# div_mod.net
KiCad netlist of a schematic drawn in EAGLE
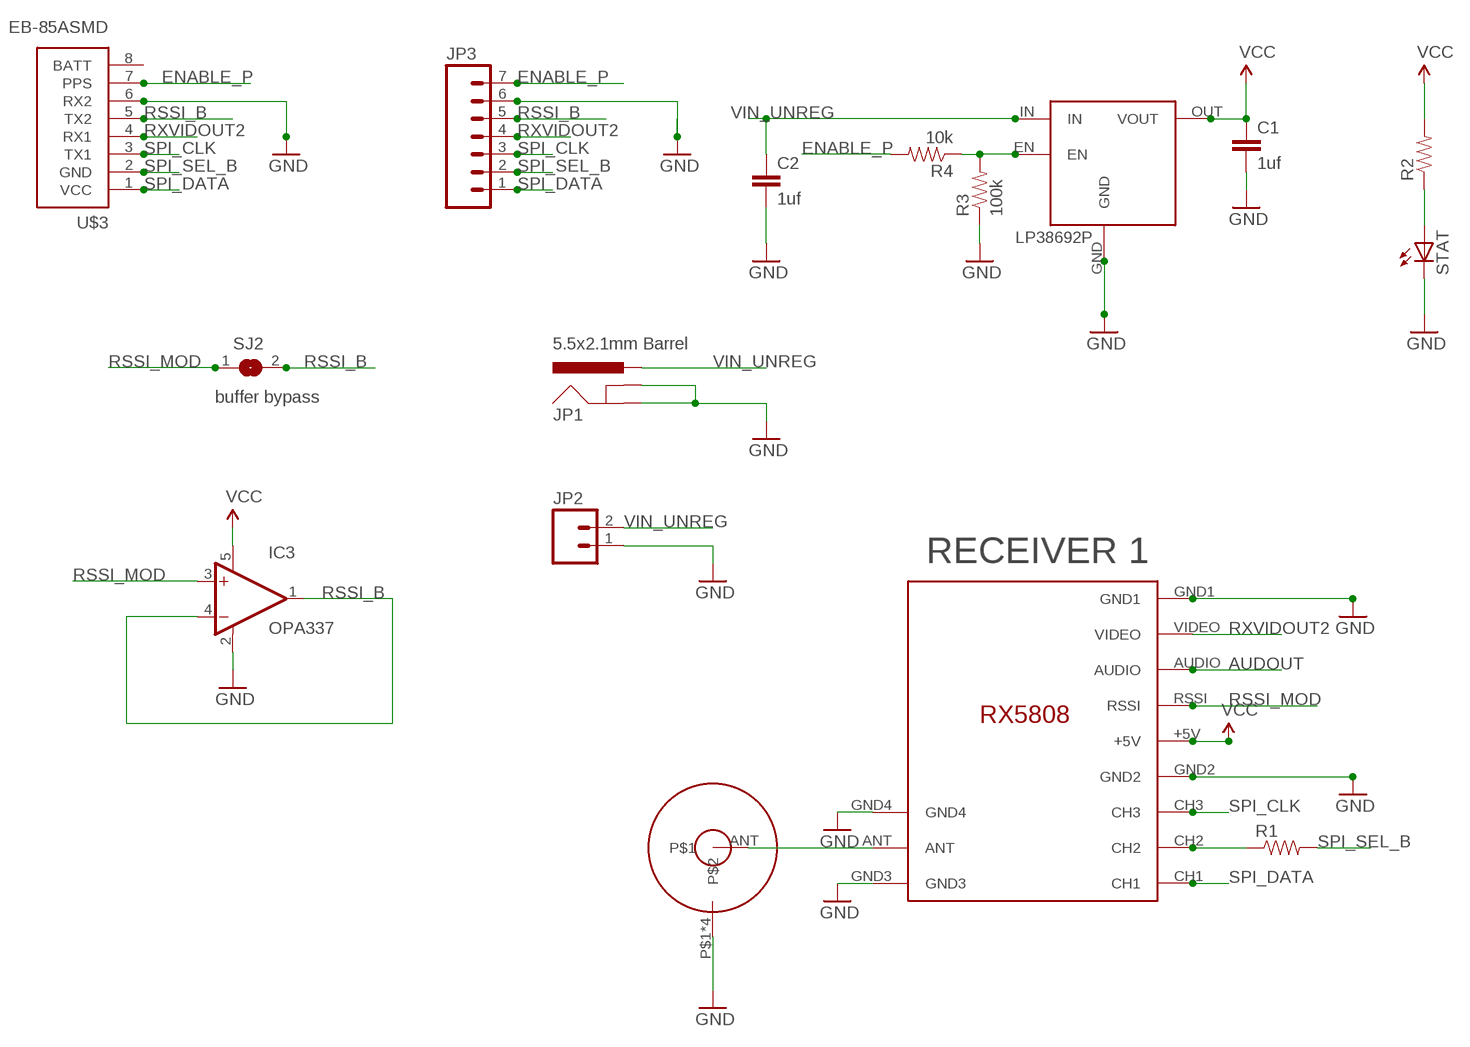
[diagram p0: schematic, sheet 1]

(export (version "E")
  (design (tool "Eeschema 10.0.6"))
  (components
    (comp (ref "C1")
      (value "1uf")
      (footprint "eagle-import:0805")
      (libsource (lib "eagle-import") (part "CAP0805"))
    )
    (comp (ref "C2")
      (value "1uf")
      (footprint "eagle-import:0805")
      (libsource (lib "eagle-import") (part "CAP0805"))
    )
    (comp (ref "IC3")
      (value "OPA336N")
      (footprint "eagle-import:SOT23-5")
      (fields (field (name "MPN") "OPA336NA"))
      (libsource (lib "eagle-import") (part "OPA336N"))
    )
    (comp (ref "JP1")
      (value "5.5x2.1mm Barrel")
      (footprint "eagle-import:POWER_JACK_SMD")
      (libsource (lib "eagle-import") (part "POWER_JACKSMD"))
    )
    (comp (ref "JP2")
      (value "M02PTH")
      (footprint "eagle-import:1X02")
      (libsource (lib "eagle-import") (part "M02PTH"))
    )
    (comp (ref "JP3")
      (value "M07")
      (footprint "eagle-import:1X07")
      (libsource (lib "eagle-import") (part "M07"))
    )
    (comp (ref "R1")
      (value "RESISTOR0805-RES")
      (footprint "eagle-import:0805")
      (libsource (lib "eagle-import") (part "RESISTOR0805-RES"))
    )
    (comp (ref "R2")
      (value "RESISTOR0805-RES")
      (footprint "eagle-import:0805")
      (libsource (lib "eagle-import") (part "RESISTOR0805-RES"))
    )
    (comp (ref "R3")
      (value "100k")
      (footprint "eagle-import:0805")
      (libsource (lib "eagle-import") (part "RESISTOR0805-RES"))
    )
    (comp (ref "R4")
      (value "10k")
      (footprint "eagle-import:0805")
      (libsource (lib "eagle-import") (part "RESISTOR0805-RES"))
    )
    (comp (ref "RECEIVER_A")
      (value "RX5808_A")
      (footprint "eagle-import:RX5808")
      (libsource (lib "eagle-import") (part "RX5808"))
    )
    (comp (ref "SJ2") (value "SJ") (footprint "eagle-import:SJ") (libsource (lib "eagle-import") (part "SJ")))
    (comp (ref "STAT")
      (value "LEDCHIP-LED0805")
      (footprint "eagle-import:CHIP-LED0805")
      (libsource (lib "eagle-import") (part "LEDCHIP-LED0805"))
    )
    (comp (ref "U$1")
      (value "SMA_ANTENNA")
      (footprint "eagle-import:SMA_CONNECTOR")
      (libsource (lib "eagle-import") (part "SMA_ANTENNA"))
    )
    (comp (ref "U$3")
      (value "EB-85ASMD")
      (footprint "eagle-import:EB-85A")
      (libsource (lib "eagle-import") (part "EB-85ASMD"))
    )
    (comp (ref "V1")
      (value "LP38692P")
      (footprint "eagle-import:TO252-51")
      (libsource (lib "eagle-import") (part "LP38692P"))
    )
  )
  (nets
    (net (code "1") (name "/AUDOUT") (class "Default")
      (node (ref "RECEIVER_A") (pin "AUDIO") (pinfunction "AUDIO_AUDIO") (pintype "bidirectional"))
    )
    (net (code "2") (name "/BATT") (class "Default")
      (node (ref "U$3") (pin "8") (pinfunction "BATT_8") (pintype "power_in"))
    )
    (net (code "3") (name "/ENABLE_P") (class "Default")
      (node (ref "JP3") (pin "7") (pinfunction "7_7") (pintype "passive"))
      (node (ref "R4") (pin "2") (pinfunction "2_2") (pintype "passive"))
      (node (ref "U$3") (pin "7") (pinfunction "PPS_7") (pintype "output"))
    )
    (net (code "4") (name "/RSSI_B") (class "Default")
      (node (ref "IC3") (pin "1") (pinfunction "OUT_1") (pintype "output"))
      (node (ref "IC3") (pin "4") (pinfunction "-IN_4") (pintype "input"))
      (node (ref "JP3") (pin "5") (pinfunction "5_5") (pintype "passive"))
      (node (ref "SJ2") (pin "2") (pinfunction "2_2") (pintype "passive"))
      (node (ref "U$3") (pin "5") (pinfunction "TX2_5") (pintype "output"))
    )
    (net (code "5") (name "/RSSI_MOD") (class "Default")
      (node (ref "IC3") (pin "3") (pinfunction "+IN_3") (pintype "input"))
      (node (ref "RECEIVER_A") (pin "RSSI") (pinfunction "RSSI_RSSI") (pintype "bidirectional"))
      (node (ref "SJ2") (pin "1") (pinfunction "1_1") (pintype "passive"))
    )
    (net (code "6") (name "/RXVIDOUT2") (class "Default")
      (node (ref "JP3") (pin "4") (pinfunction "4_4") (pintype "passive"))
      (node (ref "RECEIVER_A") (pin "VIDEO") (pinfunction "VIDEO_VIDEO") (pintype "bidirectional"))
      (node (ref "U$3") (pin "4") (pinfunction "RX1_4") (pintype "input"))
    )
    (net (code "7") (name "/SPI_CLK") (class "Default")
      (node (ref "JP3") (pin "3") (pinfunction "3_3") (pintype "passive"))
      (node (ref "RECEIVER_A") (pin "CH3") (pinfunction "CH3_CH3") (pintype "bidirectional"))
      (node (ref "U$3") (pin "3") (pinfunction "TX1_3") (pintype "output"))
    )
    (net (code "8") (name "/SPI_DATA") (class "Default")
      (node (ref "JP3") (pin "1") (pinfunction "1_1") (pintype "passive"))
      (node (ref "RECEIVER_A") (pin "CH1") (pinfunction "CH1_CH1") (pintype "bidirectional"))
      (node (ref "U$3") (pin "1") (pinfunction "VCC_1") (pintype "power_in"))
    )
    (net (code "9") (name "/SPI_SEL_B") (class "Default")
      (node (ref "JP3") (pin "2") (pinfunction "2_2") (pintype "passive"))
      (node (ref "R1") (pin "2") (pinfunction "2_2") (pintype "passive"))
      (node (ref "U$3") (pin "2") (pinfunction "GND_2") (pintype "power_in"))
    )
    (net (code "10") (name "/VIN_UNREG") (class "Default")
      (node (ref "C2") (pin "1") (pinfunction "1_1") (pintype "passive"))
      (node (ref "JP1") (pin "VIN0") (pinfunction "PWR_VIN0") (pintype "bidirectional"))
      (node (ref "JP2") (pin "2") (pinfunction "2_2") (pintype "passive"))
      (node (ref "V1") (pin "IN") (pinfunction "IN_IN") (pintype "bidirectional"))
    )
    (net (code "11") (name "GND") (class "Default")
      (node (ref "C1") (pin "2") (pinfunction "2_2") (pintype "passive"))
      (node (ref "C2") (pin "2") (pinfunction "2_2") (pintype "passive"))
      (node (ref "IC3") (pin "2") (pinfunction "V-_2") (pintype "power_in"))
      (node (ref "JP1") (pin "GND") (pinfunction "GNDBREAK_GND") (pintype "bidirectional"))
      (node (ref "JP1") (pin "P$4") (pinfunction "GND_P$4") (pintype "bidirectional"))
      (node (ref "JP2") (pin "1") (pinfunction "1_1") (pintype "passive"))
      (node (ref "JP3") (pin "6") (pinfunction "6_6") (pintype "passive"))
      (node (ref "R3") (pin "1") (pinfunction "1_1") (pintype "passive"))
      (node (ref "RECEIVER_A") (pin "GND1") (pinfunction "GND1_GND1") (pintype "bidirectional"))
      (node (ref "RECEIVER_A") (pin "GND2") (pinfunction "GND2_GND2") (pintype "bidirectional"))
      (node (ref "RECEIVER_A") (pin "GND3") (pinfunction "GND3_GND3") (pintype "bidirectional"))
      (node (ref "RECEIVER_A") (pin "GND4") (pinfunction "GND4_GND4") (pintype "bidirectional"))
      (node (ref "STAT") (pin "C") (pinfunction "C_C") (pintype "passive"))
      (node (ref "U$1") (pin "P$1") (pinfunction "P$2_P$1") (pintype "bidirectional"))
      (node (ref "U$1") (pin "P$2") (pinfunction "P$2_P$2") (pintype "bidirectional"))
      (node (ref "U$1") (pin "P$3") (pinfunction "P$2_P$3") (pintype "bidirectional"))
      (node (ref "U$1") (pin "P$4") (pinfunction "P$2_P$4") (pintype "bidirectional"))
      (node (ref "U$3") (pin "6") (pinfunction "RX2_6") (pintype "input"))
      (node (ref "V1") (pin "GND") (pinfunction "GND_GND") (pintype "bidirectional"))
    )
    (net (code "12") (name "Net-(R1-Pad1)") (class "Default")
      (node (ref "R1") (pin "1") (pinfunction "1_1") (pintype "passive"))
      (node (ref "RECEIVER_A") (pin "CH2") (pinfunction "CH2_CH2") (pintype "bidirectional"))
    )
    (net (code "13") (name "Net-(R2-Pad1)") (class "Default")
      (node (ref "R2") (pin "1") (pinfunction "1_1") (pintype "passive"))
      (node (ref "STAT") (pin "A") (pinfunction "A_A") (pintype "passive"))
    )
    (net (code "14") (name "Net-(R3-Pad2)") (class "Default")
      (node (ref "R3") (pin "2") (pinfunction "2_2") (pintype "passive"))
      (node (ref "R4") (pin "1") (pinfunction "1_1") (pintype "passive"))
      (node (ref "V1") (pin "EN") (pinfunction "EN_EN") (pintype "bidirectional"))
    )
    (net (code "15") (name "Net-(U$1-P$1)") (class "Default")
      (node (ref "RECEIVER_A") (pin "ANT") (pinfunction "ANT_ANT") (pintype "bidirectional"))
      (node (ref "U$1") (pin "ANT") (pinfunction "P$1_ANT") (pintype "bidirectional"))
    )
    (net (code "16") (name "VCC") (class "Default")
      (node (ref "C1") (pin "1") (pinfunction "1_1") (pintype "passive"))
      (node (ref "IC3") (pin "5") (pinfunction "V+_5") (pintype "power_in"))
      (node (ref "R2") (pin "2") (pinfunction "2_2") (pintype "passive"))
      (node (ref "RECEIVER_A") (pin "+5V") (pinfunction "+5V_+5V") (pintype "bidirectional"))
      (node (ref "V1") (pin "OUT") (pinfunction "VOUT_OUT") (pintype "bidirectional"))
    )
  )
)
